# LED_1edge.net
KiCad netlist of a schematic drawn in Altium Designer
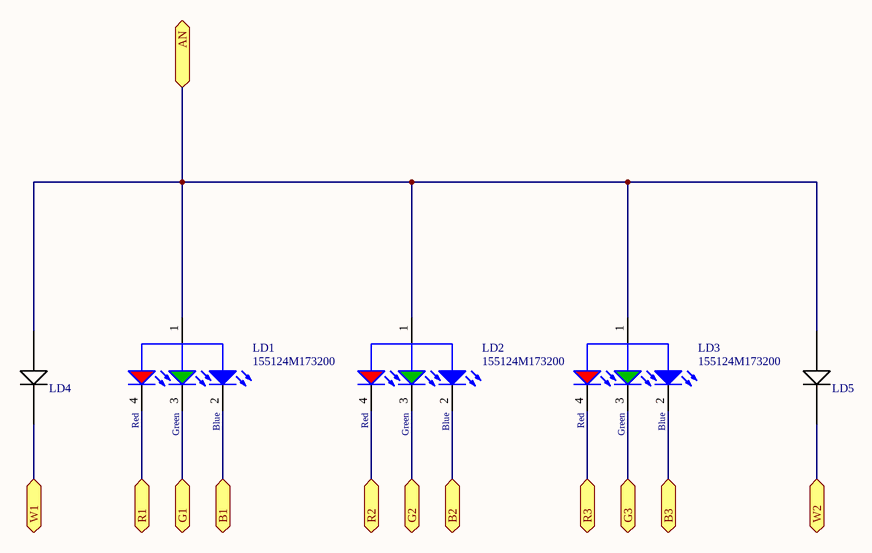
[diagram p0: LED_1edge.SchDoc]

(export (version "E")
  (design (tool "Eeschema 10.0.6"))
  (components
    (comp (ref "LD1")
      (value "155124M173200")
      (footprint "WL-SFSW_1204")
      (description "WL-SFSW SMD Full-color Side view Waterclear")
      (fields (field (name "PUBLISHER") "Wurth Elektronik"))
      (libsource (lib "WL-SFSW") (part "155124M173200"))
    )
    (comp (ref "LD2")
      (value "155124M173200")
      (footprint "WL-SFSW_1204")
      (description "WL-SFSW SMD Full-color Side view Waterclear")
      (fields (field (name "PUBLISHER") "Wurth Elektronik"))
      (libsource (lib "WL-SFSW") (part "155124M173200"))
    )
    (comp (ref "LD3")
      (value "155124M173200")
      (footprint "WL-SFSW_1204")
      (description "WL-SFSW SMD Full-color Side view Waterclear")
      (fields (field (name "PUBLISHER") "Wurth Elektronik"))
      (libsource (lib "WL-SFSW") (part "155124M173200"))
    )
    (comp (ref "LD4")
      (value "LTW-008ZDCG")
      (footprint "LTW-008ZDCG")
      (description "LED WHITE 2SMD R/A")
      (libsource (lib "snowflake") (part "LTW-008ZDCG"))
    )
    (comp (ref "LD5")
      (value "LTW-008ZDCG")
      (footprint "LTW-008ZDCG")
      (description "LED WHITE 2SMD R/A")
      (libsource (lib "snowflake") (part "LTW-008ZDCG"))
    )
  )
  (nets
    (net (code "1") (name "/AN") (class "Default")
      (node (ref "LD1") (pin "1") (pinfunction "A_1") (pintype "passive"))
      (node (ref "LD2") (pin "1") (pinfunction "A_1") (pintype "passive"))
      (node (ref "LD3") (pin "1") (pinfunction "A_1") (pintype "passive"))
      (node (ref "LD4") (pin "2") (pinfunction "K_2") (pintype "passive"))
      (node (ref "LD5") (pin "2") (pinfunction "K_2") (pintype "passive"))
    )
    (net (code "2") (name "/B1") (class "Default")
      (node (ref "LD1") (pin "2") (pinfunction "K_2") (pintype "passive"))
    )
    (net (code "3") (name "/B2") (class "Default")
      (node (ref "LD2") (pin "2") (pinfunction "K_2") (pintype "passive"))
    )
    (net (code "4") (name "/B3") (class "Default")
      (node (ref "LD3") (pin "2") (pinfunction "K_2") (pintype "passive"))
    )
    (net (code "5") (name "/G1") (class "Default")
      (node (ref "LD1") (pin "3") (pinfunction "K_3") (pintype "passive"))
    )
    (net (code "6") (name "/G2") (class "Default")
      (node (ref "LD2") (pin "3") (pinfunction "K_3") (pintype "passive"))
    )
    (net (code "7") (name "/G3") (class "Default")
      (node (ref "LD3") (pin "3") (pinfunction "K_3") (pintype "passive"))
    )
    (net (code "8") (name "/R1") (class "Default")
      (node (ref "LD1") (pin "4") (pinfunction "K_4") (pintype "passive"))
    )
    (net (code "9") (name "/R2") (class "Default")
      (node (ref "LD2") (pin "4") (pinfunction "K_4") (pintype "passive"))
    )
    (net (code "10") (name "/R3") (class "Default")
      (node (ref "LD3") (pin "4") (pinfunction "K_4") (pintype "passive"))
    )
    (net (code "11") (name "/W1") (class "Default")
      (node (ref "LD4") (pin "1") (pinfunction "A_1") (pintype "passive"))
    )
    (net (code "12") (name "/W2") (class "Default")
      (node (ref "LD5") (pin "1") (pinfunction "A_1") (pintype "passive"))
    )
  )
)
